# dcb_single_input.net
KiCad netlist of a schematic drawn in Altium Designer
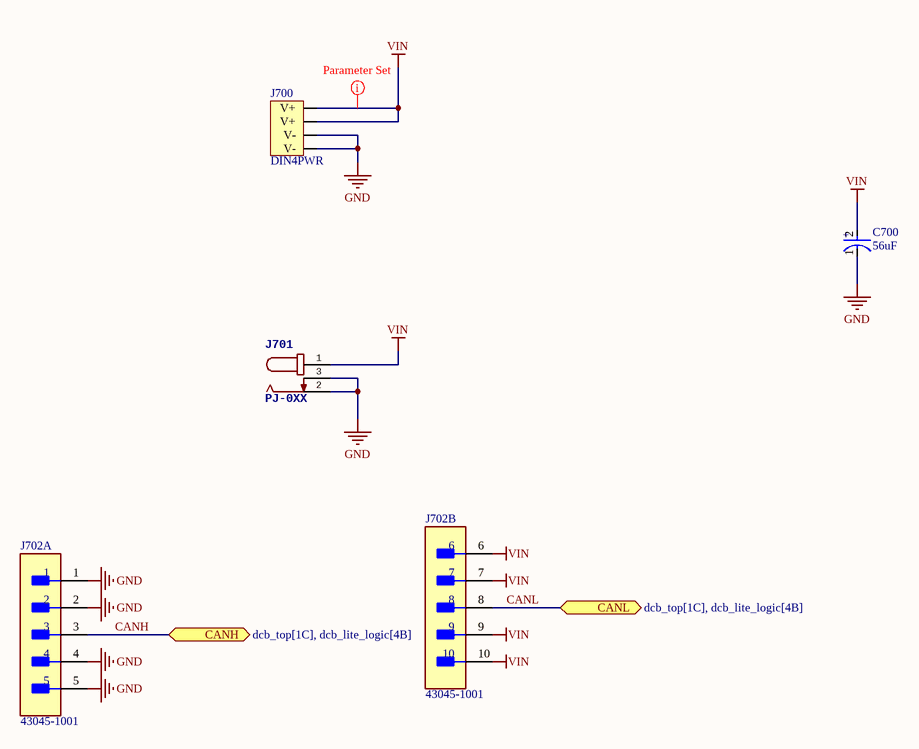
[diagram p0: dcb_single_input.SchDoc]

(export (version "E")
  (design (tool "Eeschema 10.0.6"))
  (components
    (comp (ref "C700")
      (value "56uF")
      (footprint "FP-FKG-MFG")
      (description "Cap Aluminum 56uF 63V 20% (10 X 10.2mm) SMD 0.03 Ohm 1800mA 5000h 105 C Embossed T/R")
      (fields (field (name "TOLERANCE") "20%") (field (name "VOLTAGE") "63V"))
      (libsource (lib "StackFoundry LLC") (part "203bc49f2ac43e59fd269a8c329ed05"))
    )
    (comp (ref "J700")
      (value "DIN4PWR")
      (footprint "PD40S")
      (libsource (lib "StackFoundry LLC") (part "DIN4PWR"))
    )
    (comp (ref "J701")
      (value "PJ-0XX")
      (footprint "CUI-PJ-002A_V")
      (description "2.0 x 6.5 mm, 2.5 A, Horizontal, Through Hole, Dc Power Jack Connector")
      (libsource (lib "StackFoundry LLC") (part "Symbol"))
    )
    (comp (ref "J702")
      (value "43045-1001")
      (footprint "FP-43045-1001-MFG")
      (description "Connector Wire to Board Header 10 Position 3 mm Solder Right Angle Thru-Hole Micro-Fit 3.0™")
      (libsource (lib "StackFoundry LLC") (part "de255ff815dec4fe6d5caee7def00c9"))
    )
  )
  (nets
    (net (code "1") (name "/CANH") (class "Default")
      (node (ref "J702") (pin "3") (pinfunction "3_3") (pintype "passive"))
    )
    (net (code "2") (name "/CANL") (class "Default")
      (node (ref "J702") (pin "8") (pinfunction "8_8") (pintype "passive"))
    )
    (net (code "3") (name "GND") (class "Default")
      (node (ref "C700") (pin "1") (pinfunction "C_1") (pintype "passive"))
      (node (ref "J700") (pin "1") (pinfunction "V-_1") (pintype "power_in"))
      (node (ref "J700") (pin "3") (pinfunction "V-_3") (pintype "power_in"))
      (node (ref "J701") (pin "2") (pinfunction "2_2") (pintype "passive"))
      (node (ref "J701") (pin "3") (pinfunction "3_3") (pintype "passive"))
      (node (ref "J702") (pin "1") (pinfunction "1_1") (pintype "passive"))
      (node (ref "J702") (pin "2") (pinfunction "2_2") (pintype "passive"))
      (node (ref "J702") (pin "4") (pinfunction "4_4") (pintype "passive"))
      (node (ref "J702") (pin "5") (pinfunction "5_5") (pintype "passive"))
    )
    (net (code "4") (name "VIN") (class "Default")
      (node (ref "C700") (pin "2") (pinfunction "A_2") (pintype "passive"))
      (node (ref "J700") (pin "2") (pinfunction "V+_2") (pintype "power_in"))
      (node (ref "J700") (pin "4") (pinfunction "V+_4") (pintype "power_in"))
      (node (ref "J701") (pin "1") (pinfunction "1_1") (pintype "passive"))
      (node (ref "J702") (pin "10") (pinfunction "10_10") (pintype "passive"))
      (node (ref "J702") (pin "6") (pinfunction "6_6") (pintype "passive"))
      (node (ref "J702") (pin "7") (pinfunction "7_7") (pintype "passive"))
      (node (ref "J702") (pin "9") (pinfunction "9_9") (pintype "passive"))
    )
  )
)
